# HV_Box_Connector_Board.net
KiCad netlist of a schematic drawn in Altium Designer
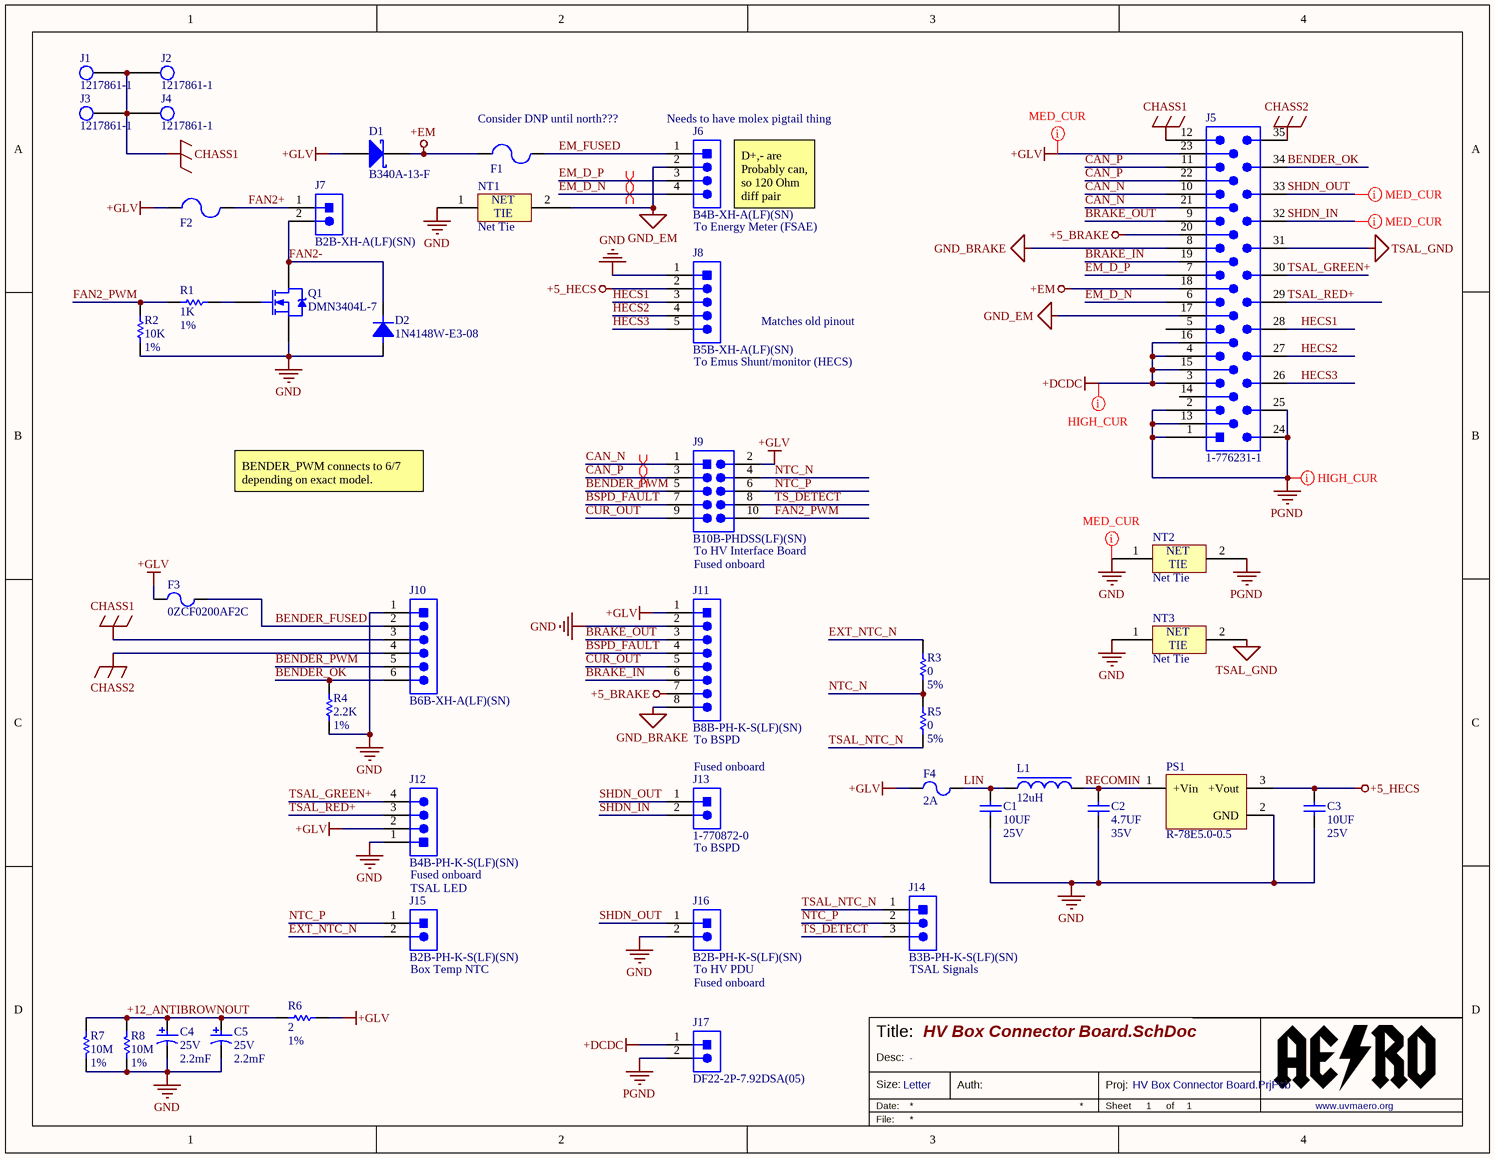
[diagram p0: HV Box Connector Board.SchDoc]

(export (version "E")
  (design (tool "Eeschema 10.0.6"))
  (components
    (comp (ref "C1")
      (value "CAP 0603 10UF 25V 20% X5R")
      (footprint "0603_CAP")
      (description "Capacitor Surface Mount 0603 Footprint 10UF 25V 20% Tolerance Ceramic X5R")
      (fields
        (field (name "VAL") "10UF")
        (field (name "VOL") "25V")
        (field (name "MANUFACTURER") "Various")
        (field (name "VOLTAGE") "25V")
      )
      (libsource (lib "Passive Components") (part "cap"))
    )
    (comp (ref "C2")
      (value "CAP 0603 4.7UF 35V 10% X5R")
      (footprint "0603_CAP")
      (description "Capacitor Surface Mount 0603 Footprint 47UF 35V 10% Tolerance Ceramic X5R")
      (fields
        (field (name "VAL") "4.7UF")
        (field (name "VOL") "35V")
        (field (name "MANUFACTURER") "Various")
        (field (name "VOLTAGE") "35V")
      )
      (libsource (lib "Passive Components") (part "cap"))
    )
    (comp (ref "C3")
      (value "CAP 0603 10UF 25V 20% X5R")
      (footprint "0603_CAP")
      (description "Capacitor Surface Mount 0603 Footprint 10UF 25V 20% Tolerance Ceramic X5R")
      (fields
        (field (name "VAL") "10UF")
        (field (name "VOL") "25V")
        (field (name "MANUFACTURER") "Various")
        (field (name "VOLTAGE") "25V")
      )
      (libsource (lib "Passive Components") (part "cap"))
    )
    (comp (ref "C4")
      (value "URS1E222MHD")
      (footprint "Nichicon_18x15")
      (description "2200µF 25V Aluminum Electrolytic Capacitors Radial, Can  2000 Hrs @ 85°C")
      (fields
        (field (name "MANUFACTURER") "Nichicon")
        (field (name "TOLERANCE") "20%")
        (field (name "VOLTAGE RATING (DC)") "25V")
        (field (name "CAPACITANCE") "2.2mF")
      )
      (libsource (lib "AERO Parts") (part "URS1E222MHD"))
    )
    (comp (ref "C5")
      (value "URS1E222MHD")
      (footprint "Nichicon_18x15")
      (description "2200µF 25V Aluminum Electrolytic Capacitors Radial, Can  2000 Hrs @ 85°C")
      (fields
        (field (name "MANUFACTURER") "Nichicon")
        (field (name "TOLERANCE") "20%")
        (field (name "VOLTAGE RATING (DC)") "25V")
        (field (name "CAPACITANCE") "2.2mF")
      )
      (libsource (lib "AERO Parts") (part "URS1E222MHD"))
    )
    (comp (ref "D1")
      (value "B340A-13-F")
      (footprint "DIOD-SMA-2_V")
      (libsource (lib "Altium Content Vault") (part "DSKY-AK-2"))
    )
    (comp (ref "D2")
      (value "1N4148W-E3-08")
      (footprint "Vishay_1N4148W-E3-08")
      (description "Diode Standard 75V 150mA Surface Mount SOD-123")
      (fields (field (name "MANUFACTURER") "Vishay"))
      (libsource (lib "AERO Parts") (part "1N4148W-E3-08"))
    )
    (comp (ref "F1")
      (value "NANOSMDC050F/13.2-2")
      (footprint "1206_FUSE_40H")
      (description "610 mA 13.2 VDC PTC resettable fuse 1206 footprint")
      (fields (field (name "MANUFACTURER") "Tyco"))
      (libsource (lib "Passive Components") (part "fuse"))
    )
    (comp (ref "F2")
      (value "NANOSMDC050F/13.2-2")
      (footprint "1206_FUSE_40H")
      (description "610 mA 13.2 VDC PTC resettable fuse 1206 footprint")
      (fields (field (name "MANUFACTURER") "Tyco"))
      (libsource (lib "Passive Components") (part "fuse"))
    )
    (comp (ref "F3")
      (value "0ZCF0200AF2C")
      (footprint "Bel_0ZCF0200AF2C_0")
      (description "Polymeric PTC Resettable Fuse 24V 2A Ih Surface Mount 2920 (7351 Metric), Concave")
      (fields (field (name "MANUFACTURER") "Bel"))
      (libsource (lib "AERO Parts") (part "0ZCF0200AF2C"))
    )
    (comp (ref "F4")
      (value "0ZCF0200AF2C")
      (footprint "Bel_0ZCF0200AF2C_0")
      (description "Polymeric PTC Resettable Fuse 24V 2A Ih Surface Mount 2920 (7351 Metric), Concave")
      (fields (field (name "HOLD CURRENT") "2A") (field (name "MANUFACTURER") "Bel"))
      (libsource (lib "AERO Parts") (part "0ZCF0200AF2C"))
    )
    (comp (ref "J1")
      (value "1217861-1")
      (footprint "te-1217861-1")
      (description "CONN TAB .250 STR QC TIN PCB")
      (libsource (lib "AERO Parts") (part "1217861-1"))
    )
    (comp (ref "J2")
      (value "1217861-1")
      (footprint "te-1217861-1")
      (description "CONN TAB .250 STR QC TIN PCB")
      (libsource (lib "AERO Parts") (part "1217861-1"))
    )
    (comp (ref "J3")
      (value "1217861-1")
      (footprint "te-1217861-1")
      (description "CONN TAB .250 STR QC TIN PCB")
      (libsource (lib "AERO Parts") (part "1217861-1"))
    )
    (comp (ref "J4")
      (value "1217861-1")
      (footprint "te-1217861-1")
      (description "CONN TAB .250 STR QC TIN PCB")
      (libsource (lib "AERO Parts") (part "1217861-1"))
    )
    (comp (ref "J5")
      (value "1-776231-1")
      (footprint "TE_1-776231-1")
      (description "Connector Header Panel Mount, Through Hole 35 position 0.157\" (4.00mm)")
      (fields (field (name "MANUFACTURER") "TE Connectivity"))
      (libsource (lib "AERO Parts") (part "1-776231-1"))
    )
    (comp (ref "J6")
      (value "B4B-XH-A(LF)(SN)")
      (footprint "B4B-XH-A(LF)(SN)")
      (description "Connector Header Through Hole 4 position 0.098\" (2.50mm)")
      (fields (field (name "MANUFACTURER") "JST"))
      (libsource (lib "AERO Parts") (part "B4B-XH-A(LF)(SN)"))
    )
    (comp (ref "J7")
      (value "B2B-XH-A(LF)(SN)")
      (footprint "B2B-XH-A(LF)(SN)")
      (description "CONN HEADER VERT 2POS 2.5MM")
      (fields (field (name "MANUFACTURER") "JST"))
      (libsource (lib "AERO Parts") (part "B2B-XH-A(LF)(SN)"))
    )
    (comp (ref "J8")
      (value "B5B-XH-A(LF)(SN)")
      (footprint "JST_B5B-XH-A_LF_SN_0")
      (description "Connector Header Through Hole 5 position 0.098\" (2.50mm)")
      (fields (field (name "MANUFACTURER") "JST"))
      (libsource (lib "AERO Parts") (part "B5B-XH-A(LF)(SN)"))
    )
    (comp (ref "J9")
      (value "B10B-PHDSS(LF)(SN)")
      (footprint "B10B-PHDSS")
      (description "Connector Header Through Hole 10 position 0.079\" (2.00mm)")
      (fields (field (name "MANUFACTURER") "JST"))
      (libsource (lib "AERO Parts") (part "B10B-PHDSS(LF)(SN)"))
    )
    (comp (ref "J10")
      (value "B6B-XH-A(LF)(SN)")
      (footprint "CONN_B6B-XH-A(LF")
      (description "Connector Header Through Hole 6 position 0.098\" (2.50mm)")
      (fields (field (name "MANUFACTURER") "JST") (field (name "MANUFACTURER PART NUMBER") "B6BXHA(LF)(SN)"))
      (libsource (lib "AERO Parts") (part "B6B-XH-A(LF)(SN)"))
    )
    (comp (ref "J11")
      (value "B8B-PH-K-S(LF)(SN)")
      (footprint "B8B-PH-K")
      (description "Connector Header Through Hole 8 position 0.079\" (2.00mm)")
      (libsource (lib "AERO Parts") (part "B8B-PH-K-S(LF)(SN)"))
    )
    (comp (ref "J12")
      (value "B4B-PH-K-S(LF)(SN)")
      (footprint "B4B-PH-K")
      (fields (field (name "MANUFACTURER") "JST"))
      (libsource (lib "AERO Parts") (part "B4B-PH-K-S(LF)(SN)"))
    )
    (comp (ref "J13")
      (value "1-770872-0")
      (footprint "CON2_1X2_P163_VM")
      (description "Connector Header Through Hole 2 position 0.163\" (4.14mm)")
      (fields
        (field (name "MANUFACTURER") "TE Connectivity")
        (field (name "COPYRIGHT") "Copyright (C) 2018 Accelerated Designs. All rights reserved")
      )
      (libsource (lib "AERO Parts") (part "1-770872-0"))
    )
    (comp (ref "J14")
      (value "B3B-PH-K-S(LF)(SN)")
      (footprint "B3B-PH-K")
      (description "Connector Header Through Hole 3 position 0.079\" (2.00mm)")
      (fields (field (name "MANUFACTURER") "JST"))
      (libsource (lib "AERO Parts") (part "B3B-PH-K-S(LF)(SN)"))
    )
    (comp (ref "J15")
      (value "B2B-PH-K-S(LF)(SN)")
      (footprint "JST_Sales_America_Inc._B2B-PH-K-S_LF_SN_0")
      (description "Connector Header Through Hole 2 position 0.079\" (2.00mm)")
      (fields (field (name "MANUFACTURER") "JST") (field (name "MANUFACTURER PART NUMBER") "B2BPHKSLFSN"))
      (libsource (lib "AERO Parts") (part "B2B-PH-K-S(LF)(SN)"))
    )
    (comp (ref "J16")
      (value "B2B-PH-K-S(LF)(SN)")
      (footprint "JST_Sales_America_Inc._B2B-PH-K-S_LF_SN_0")
      (description "Connector Header Through Hole 2 position 0.079\" (2.00mm)")
      (fields (field (name "MANUFACTURER") "JST") (field (name "MANUFACTURER PART NUMBER") "B2BPHKSLFSN"))
      (libsource (lib "AERO Parts") (part "B2B-PH-K-S(LF)(SN)"))
    )
    (comp (ref "J17")
      (value "DF22-2P-7.92DSA(05)")
      (footprint "DF22-2P-7.92DSA_05_0")
      (description "Connector Header Through Hole 2 position 0.312\" (7.92mm)")
      (fields (field (name "MANUFACTURER") "Hirose"))
      (libsource (lib "AERO Parts") (part "DF22-2P-7.92DSA(05)"))
    )
    (comp (ref "L1")
      (value "1225AS-H-120M=P2")
      (footprint "IND_1225AS-H-120M=P2")
      (description "1µH Shielded Wirewound Inductor 15A 4.6mOhm Nonstandard")
      (fields
        (field (name "MANUFACTURER") "Murata")
        (field (name "TOLERANCE") "20%")
        (field (name "INDUCTANCE") "12uH")
      )
      (libsource (lib "AERO Parts") (part "1225AS-H-120M=P2"))
    )
    (comp (ref "NT1")
      (value "Net Tie")
      (footprint "20MIL_TIE")
      (description "Net Tie (No BOM)")
      (libsource (lib "AERO Parts") (part "NET TIE"))
    )
    (comp (ref "NT2")
      (value "Net Tie")
      (footprint "60MIL_TIE")
      (description "Net Tie (No BOM)")
      (libsource (lib "AERO Parts") (part "NET TIE"))
    )
    (comp (ref "NT3")
      (value "Net Tie")
      (footprint "20MIL_TIE")
      (description "Net Tie (No BOM)")
      (libsource (lib "AERO Parts") (part "NET TIE"))
    )
    (comp (ref "PS1")
      (value "R-78E5.0-0.5")
      (footprint "R-78E5.0")
      (description "IC Linear Regulator Replacement DC DC Converter 1 Output 5V 500mA 7V - 28V Input")
      (fields (field (name "DIGIKEY PART NUMBER") "945-1648-5-ND") (field (name "MANUFACTURER") "RECOM"))
      (libsource (lib "AERO Parts") (part "R-78E5.0-0.5"))
    )
    (comp (ref "Q1")
      (value "DMN3404L-7")
      (footprint "SOT23-FET-DI")
      (description "N-Channel 30V 5.8A (Ta) 720mW (Ta) Surface Mount SOT-23-3")
      (fields (field (name "MANUFACTURER") "Diodes"))
      (libsource (lib "AERO Parts") (part "DMN3404L-7"))
    )
    (comp (ref "R1")
      (value "RES 0603 1K 1%")
      (footprint "0603_RES")
      (description "Resistor Surface Mount, 1K Ohms, 0603 Footprint, 1% Tolerance 0.1W")
      (fields
        (field (name "VAL") "1K")
        (field (name "TOL") "1%")
        (field (name "MANUFACTURER") "Various")
        (field (name "TOLERANCE") "1%")
      )
      (libsource (lib "Passive Components") (part "res"))
    )
    (comp (ref "R2")
      (value "RES 0603 10K 1%")
      (footprint "0603_RES")
      (description "Resistor Surface Mount, 10K Ohms, 0603 Footprint, 1% Tolerance 0.1W")
      (fields
        (field (name "VAL") "10K")
        (field (name "TOL") "1%")
        (field (name "MANUFACTURER") "Various")
        (field (name "TOLERANCE") "1%")
      )
      (libsource (lib "Passive Components") (part "res"))
    )
    (comp (ref "R3")
      (value "RES 0603 0 5%")
      (footprint "0603_RES")
      (description "Resistor Surface Mount, 0 Ohms, 0603 Footprint, 5% Tolerance 0.1W")
      (fields
        (field (name "VAL") "0")
        (field (name "TOL") "5%")
        (field (name "MANUFACTURER") "Various")
        (field (name "TOLERANCE") "5%")
      )
      (libsource (lib "Passive Components") (part "res"))
    )
    (comp (ref "R4")
      (value "RES 0603 2.2K 1%")
      (footprint "0603_RES")
      (description "Resistor Surface Mount, 2.2K Ohms, 0603 Footprint, 1% Tolerance 0.1W")
      (fields
        (field (name "VAL") "2.2K")
        (field (name "TOL") "1%")
        (field (name "MANUFACTURER") "Various")
        (field (name "TOLERANCE") "1%")
      )
      (libsource (lib "Passive Components") (part "res"))
    )
    (comp (ref "R5")
      (value "RES 0603 0 5%")
      (footprint "0603_RES")
      (description "Resistor Surface Mount, 0 Ohms, 0603 Footprint, 5% Tolerance 0.1W")
      (fields
        (field (name "VAL") "0")
        (field (name "TOL") "5%")
        (field (name "MANUFACTURER") "Various")
        (field (name "TOLERANCE") "5%")
      )
      (libsource (lib "Passive Components") (part "res"))
    )
    (comp (ref "R6")
      (value "RES 1206 2 1%")
      (footprint "1206_RES_28H")
      (description "Resistor Surface Mount, 2 Ohms, 1206 Footprint, 1% Tolerance 0.25W")
      (fields
        (field (name "VAL") "2")
        (field (name "TOL") "1%")
        (field (name "MANUFACTURER") "Various")
        (field (name "TOLERANCE") "1%")
      )
      (libsource (lib "Passive Components") (part "res"))
    )
    (comp (ref "R7")
      (value "RES 0805 10M 1%")
      (footprint "0805_RES")
      (description "Resistor Surface Mount, 10M Ohms, 0805 Footprint, 1% Tolerance 0.125W")
      (fields
        (field (name "VAL") "10M")
        (field (name "TOL") "1%")
        (field (name "MANUFACTURER") "Various")
        (field (name "TOLERANCE") "1%")
      )
      (libsource (lib "Passive Components") (part "res"))
    )
    (comp (ref "R8")
      (value "RES 0805 10M 1%")
      (footprint "0805_RES")
      (description "Resistor Surface Mount, 10M Ohms, 0805 Footprint, 1% Tolerance 0.125W")
      (fields
        (field (name "VAL") "10M")
        (field (name "TOL") "1%")
        (field (name "MANUFACTURER") "Various")
        (field (name "TOLERANCE") "1%")
      )
      (libsource (lib "Passive Components") (part "res"))
    )
  )
  (nets
    (net (code "1") (name "+5_BRAKE") (class "Default")
      (node (ref "J11") (pin "7") (pinfunction "7_7") (pintype "passive"))
      (node (ref "J5") (pin "20") (pinfunction "20_20") (pintype "passive"))
    )
    (net (code "2") (name "+5_HECS") (class "Default")
      (node (ref "C3") (pin "2") (pinfunction "2_2") (pintype "passive"))
      (node (ref "J8") (pin "2") (pinfunction "2_2") (pintype "passive"))
      (node (ref "PS1") (pin "3") (pinfunction "+Vout_3") (pintype "power_in"))
    )
    (net (code "3") (name "+DCDC") (class "Default")
      (node (ref "J17") (pin "1") (pinfunction "1_1") (pintype "passive"))
      (node (ref "J5") (pin "15") (pinfunction "15_15") (pintype "passive"))
      (node (ref "J5") (pin "16") (pinfunction "16_16") (pintype "passive"))
      (node (ref "J5") (pin "3") (pinfunction "3_3") (pintype "passive"))
      (node (ref "J5") (pin "4") (pinfunction "4_4") (pintype "passive"))
    )
    (net (code "4") (name "+EM") (class "Default")
      (node (ref "D1") (pin "2") (pinfunction "K_2") (pintype "passive"))
      (node (ref "F1") (pin "1") (pinfunction "1_1") (pintype "passive"))
      (node (ref "J5") (pin "18") (pinfunction "18_18") (pintype "passive"))
    )
    (net (code "5") (name "+GLV") (class "Default")
      (node (ref "D1") (pin "1") (pinfunction "A_1") (pintype "passive"))
      (node (ref "F2") (pin "1") (pinfunction "1_1") (pintype "passive"))
      (node (ref "F3") (pin "1") (pinfunction "1_1") (pintype "passive"))
      (node (ref "F4") (pin "1") (pinfunction "1_1") (pintype "passive"))
      (node (ref "J11") (pin "1") (pinfunction "1_1") (pintype "passive"))
      (node (ref "J12") (pin "2") (pinfunction "2_2") (pintype "passive"))
      (node (ref "J5") (pin "23") (pinfunction "23_23") (pintype "passive"))
      (node (ref "J9") (pin "2") (pinfunction "2_2") (pintype "passive"))
      (node (ref "R6") (pin "2") (pinfunction "2_2") (pintype "passive"))
    )
    (net (code "6") (name "/+12_ANTIBROWNOUT") (class "Default")
      (node (ref "C4") (pin "1") (pinfunction "1_1") (pintype "passive"))
      (node (ref "C5") (pin "1") (pinfunction "1_1") (pintype "passive"))
      (node (ref "R6") (pin "1") (pinfunction "1_1") (pintype "passive"))
      (node (ref "R7") (pin "2") (pinfunction "2_2") (pintype "passive"))
      (node (ref "R8") (pin "2") (pinfunction "2_2") (pintype "passive"))
    )
    (net (code "7") (name "/BENDER_FUSED") (class "Default")
      (node (ref "F3") (pin "2") (pinfunction "2_2") (pintype "passive"))
      (node (ref "J10") (pin "2") (pinfunction "2_2") (pintype "passive"))
    )
    (net (code "8") (name "/BENDER_OK") (class "Default")
      (node (ref "J10") (pin "6") (pinfunction "6_6") (pintype "passive"))
      (node (ref "J5") (pin "34") (pinfunction "34_34") (pintype "passive"))
      (node (ref "R4") (pin "1") (pinfunction "1_1") (pintype "passive"))
    )
    (net (code "9") (name "/BENDER_PWM") (class "Default")
      (node (ref "J10") (pin "5") (pinfunction "5_5") (pintype "passive"))
      (node (ref "J9") (pin "5") (pinfunction "5_5") (pintype "passive"))
    )
    (net (code "10") (name "/BRAKE_IN") (class "Default")
      (node (ref "J11") (pin "6") (pinfunction "6_6") (pintype "passive"))
      (node (ref "J5") (pin "19") (pinfunction "19_19") (pintype "passive"))
    )
    (net (code "11") (name "/BRAKE_OUT") (class "Default")
      (node (ref "J11") (pin "3") (pinfunction "3_3") (pintype "passive"))
      (node (ref "J5") (pin "9") (pinfunction "9_9") (pintype "passive"))
    )
    (net (code "12") (name "/BSPD_FAULT") (class "Default")
      (node (ref "J11") (pin "4") (pinfunction "4_4") (pintype "passive"))
      (node (ref "J9") (pin "7") (pinfunction "7_7") (pintype "passive"))
    )
    (net (code "13") (name "/CAN_N") (class "Default")
      (node (ref "J5") (pin "10") (pinfunction "10_10") (pintype "passive"))
      (node (ref "J5") (pin "21") (pinfunction "21_21") (pintype "passive"))
      (node (ref "J9") (pin "1") (pinfunction "1_1") (pintype "passive"))
    )
    (net (code "14") (name "/CAN_P") (class "Default")
      (node (ref "J5") (pin "11") (pinfunction "11_11") (pintype "passive"))
      (node (ref "J5") (pin "22") (pinfunction "22_22") (pintype "passive"))
      (node (ref "J9") (pin "3") (pinfunction "3_3") (pintype "passive"))
    )
    (net (code "15") (name "/CUR_OUT") (class "Default")
      (node (ref "J11") (pin "5") (pinfunction "5_5") (pintype "passive"))
      (node (ref "J9") (pin "9") (pinfunction "9_9") (pintype "passive"))
    )
    (net (code "16") (name "/EM_D_N") (class "Default")
      (node (ref "J5") (pin "6") (pinfunction "6_6") (pintype "passive"))
      (node (ref "J6") (pin "4") (pinfunction "4_4") (pintype "passive"))
    )
    (net (code "17") (name "/EM_D_P") (class "Default")
      (node (ref "J5") (pin "7") (pinfunction "7_7") (pintype "passive"))
      (node (ref "J6") (pin "3") (pinfunction "3_3") (pintype "passive"))
    )
    (net (code "18") (name "/EM_FUSED") (class "Default")
      (node (ref "F1") (pin "2") (pinfunction "2_2") (pintype "passive"))
      (node (ref "J6") (pin "1") (pinfunction "1_1") (pintype "passive"))
    )
    (net (code "19") (name "/EXT_NTC_N") (class "Default")
      (node (ref "J15") (pin "2") (pinfunction "2_2") (pintype "passive"))
      (node (ref "R3") (pin "2") (pinfunction "2_2") (pintype "passive"))
    )
    (net (code "20") (name "/FAN2+") (class "Default")
      (node (ref "F2") (pin "2") (pinfunction "2_2") (pintype "passive"))
      (node (ref "J7") (pin "1") (pinfunction "1_1") (pintype "passive"))
    )
    (net (code "21") (name "/FAN2-") (class "Default")
      (node (ref "D2") (pin "K") (pinfunction "K_K") (pintype "passive"))
      (node (ref "J7") (pin "2") (pinfunction "2_2") (pintype "passive"))
      (node (ref "Q1") (pin "3") (pinfunction "D_3") (pintype "passive"))
    )
    (net (code "22") (name "/FAN2_PWM") (class "Default")
      (node (ref "J9") (pin "10") (pinfunction "10_10") (pintype "passive"))
      (node (ref "R1") (pin "1") (pinfunction "1_1") (pintype "passive"))
      (node (ref "R2") (pin "2") (pinfunction "2_2") (pintype "passive"))
    )
    (net (code "23") (name "/HECS1") (class "Default")
      (node (ref "J5") (pin "28") (pinfunction "28_28") (pintype "passive"))
      (node (ref "J8") (pin "3") (pinfunction "3_3") (pintype "passive"))
    )
    (net (code "24") (name "/HECS2") (class "Default")
      (node (ref "J5") (pin "27") (pinfunction "27_27") (pintype "passive"))
      (node (ref "J8") (pin "4") (pinfunction "4_4") (pintype "passive"))
    )
    (net (code "25") (name "/HECS3") (class "Default")
      (node (ref "J5") (pin "26") (pinfunction "26_26") (pintype "passive"))
      (node (ref "J8") (pin "5") (pinfunction "5_5") (pintype "passive"))
    )
    (net (code "26") (name "/LIN") (class "Default")
      (node (ref "C1") (pin "2") (pinfunction "2_2") (pintype "passive"))
      (node (ref "F4") (pin "2") (pinfunction "2_2") (pintype "passive"))
      (node (ref "L1") (pin "1") (pinfunction "1_1") (pintype "passive"))
    )
    (net (code "27") (name "/NTC_N") (class "Default")
      (node (ref "J9") (pin "4") (pinfunction "4_4") (pintype "passive"))
      (node (ref "R3") (pin "1") (pinfunction "1_1") (pintype "passive"))
      (node (ref "R5") (pin "2") (pinfunction "2_2") (pintype "passive"))
    )
    (net (code "28") (name "/NTC_P") (class "Default")
      (node (ref "J14") (pin "2") (pinfunction "2_2") (pintype "passive"))
      (node (ref "J15") (pin "1") (pinfunction "1_1") (pintype "passive"))
      (node (ref "J9") (pin "6") (pinfunction "6_6") (pintype "passive"))
    )
    (net (code "29") (name "/RECOMIN") (class "Default")
      (node (ref "C2") (pin "2") (pinfunction "2_2") (pintype "passive"))
      (node (ref "L1") (pin "2") (pinfunction "2_2") (pintype "passive"))
      (node (ref "PS1") (pin "1") (pinfunction "+Vin_1") (pintype "power_in"))
    )
    (net (code "30") (name "/SHDN_IN") (class "Default")
      (node (ref "J13") (pin "2") (pinfunction "2_2") (pintype "passive"))
      (node (ref "J5") (pin "32") (pinfunction "32_32") (pintype "passive"))
    )
    (net (code "31") (name "/SHDN_OUT") (class "Default")
      (node (ref "J13") (pin "1") (pinfunction "1_1") (pintype "passive"))
      (node (ref "J16") (pin "1") (pinfunction "1_1") (pintype "passive"))
      (node (ref "J5") (pin "33") (pinfunction "33_33") (pintype "passive"))
    )
    (net (code "32") (name "/TSAL_GREEN+") (class "Default")
      (node (ref "J12") (pin "4") (pinfunction "4_4") (pintype "passive"))
      (node (ref "J5") (pin "30") (pinfunction "30_30") (pintype "passive"))
    )
    (net (code "33") (name "/TSAL_NTC_N") (class "Default")
      (node (ref "J14") (pin "1") (pinfunction "1_1") (pintype "passive"))
      (node (ref "R5") (pin "1") (pinfunction "1_1") (pintype "passive"))
    )
    (net (code "34") (name "/TSAL_RED+") (class "Default")
      (node (ref "J12") (pin "3") (pinfunction "3_3") (pintype "passive"))
      (node (ref "J5") (pin "29") (pinfunction "29_29") (pintype "passive"))
    )
    (net (code "35") (name "/TS_DETECT") (class "Default")
      (node (ref "J14") (pin "3") (pinfunction "3_3") (pintype "passive"))
      (node (ref "J9") (pin "8") (pinfunction "8_8") (pintype "passive"))
    )
    (net (code "36") (name "CHASS1") (class "Default")
      (node (ref "J1") (pin "1a") (pinfunction "1a_1a") (pintype "passive"))
      (node (ref "J1") (pin "1b") (pinfunction "1b_1b") (pintype "passive"))
      (node (ref "J1") (pin "1c") (pinfunction "1c_1c") (pintype "passive"))
      (node (ref "J10") (pin "3") (pinfunction "3_3") (pintype "passive"))
      (node (ref "J2") (pin "1a") (pinfunction "1a_1a") (pintype "passive"))
      (node (ref "J2") (pin "1b") (pinfunction "1b_1b") (pintype "passive"))
      (node (ref "J2") (pin "1c") (pinfunction "1c_1c") (pintype "passive"))
      (node (ref "J3") (pin "1a") (pinfunction "1a_1a") (pintype "passive"))
      (node (ref "J3") (pin "1b") (pinfunction "1b_1b") (pintype "passive"))
      (node (ref "J3") (pin "1c") (pinfunction "1c_1c") (pintype "passive"))
      (node (ref "J4") (pin "1a") (pinfunction "1a_1a") (pintype "passive"))
      (node (ref "J4") (pin "1b") (pinfunction "1b_1b") (pintype "passive"))
      (node (ref "J4") (pin "1c") (pinfunction "1c_1c") (pintype "passive"))
      (node (ref "J5") (pin "12") (pinfunction "12_12") (pintype "passive"))
    )
    (net (code "37") (name "CHASS2") (class "Default")
      (node (ref "J10") (pin "4") (pinfunction "4_4") (pintype "passive"))
      (node (ref "J5") (pin "35") (pinfunction "35_35") (pintype "passive"))
    )
    (net (code "38") (name "GND") (class "Default")
      (node (ref "C1") (pin "1") (pinfunction "1_1") (pintype "passive"))
      (node (ref "C2") (pin "1") (pinfunction "1_1") (pintype "passive"))
      (node (ref "C3") (pin "1") (pinfunction "1_1") (pintype "passive"))
      (node (ref "C4") (pin "2") (pinfunction "2_2") (pintype "passive"))
      (node (ref "C5") (pin "2") (pinfunction "2_2") (pintype "passive"))
      (node (ref "D2") (pin "A") (pinfunction "A_A") (pintype "passive"))
      (node (ref "J10") (pin "1") (pinfunction "1_1") (pintype "passive"))
      (node (ref "J11") (pin "2") (pinfunction "2_2") (pintype "passive"))
      (node (ref "J12") (pin "1") (pinfunction "1_1") (pintype "passive"))
      (node (ref "J16") (pin "2") (pinfunction "2_2") (pintype "passive"))
      (node (ref "J8") (pin "1") (pinfunction "1_1") (pintype "passive"))
      (node (ref "NT1") (pin "1") (pintype "passive"))
      (node (ref "NT2") (pin "1") (pintype "passive"))
      (node (ref "NT3") (pin "1") (pintype "passive"))
      (node (ref "PS1") (pin "2") (pinfunction "GND_2") (pintype "power_in"))
      (node (ref "Q1") (pin "2") (pinfunction "S_2") (pintype "passive"))
      (node (ref "R2") (pin "1") (pinfunction "1_1") (pintype "passive"))
      (node (ref "R4") (pin "2") (pinfunction "2_2") (pintype "passive"))
      (node (ref "R7") (pin "1") (pinfunction "1_1") (pintype "passive"))
      (node (ref "R8") (pin "1") (pinfunction "1_1") (pintype "passive"))
    )
    (net (code "39") (name "GND_BRAKE") (class "Default")
      (node (ref "J11") (pin "8") (pinfunction "8_8") (pintype "passive"))
      (node (ref "J5") (pin "8") (pinfunction "8_8") (pintype "passive"))
    )
    (net (code "40") (name "GND_EM") (class "Default")
      (node (ref "J5") (pin "17") (pinfunction "17_17") (pintype "passive"))
      (node (ref "J6") (pin "2") (pinfunction "2_2") (pintype "passive"))
      (node (ref "NT1") (pin "2") (pintype "passive"))
    )
    (net (code "41") (name "Net-(Q1-G)") (class "Default")
      (node (ref "Q1") (pin "1") (pinfunction "G_1") (pintype "passive"))
      (node (ref "R1") (pin "2") (pinfunction "2_2") (pintype "passive"))
    )
    (net (code "42") (name "PGND") (class "Default")
      (node (ref "J17") (pin "2") (pinfunction "2_2") (pintype "passive"))
      (node (ref "J5") (pin "1") (pinfunction "1_1") (pintype "passive"))
      (node (ref "J5") (pin "13") (pinfunction "13_13") (pintype "passive"))
      (node (ref "J5") (pin "2") (pinfunction "2_2") (pintype "passive"))
      (node (ref "J5") (pin "24") (pinfunction "24_24") (pintype "passive"))
      (node (ref "J5") (pin "25") (pinfunction "25_25") (pintype "passive"))
      (node (ref "NT2") (pin "2") (pintype "passive"))
    )
    (net (code "43") (name "TSAL_GND") (class "Default")
      (node (ref "J5") (pin "31") (pinfunction "31_31") (pintype "passive"))
      (node (ref "NT3") (pin "2") (pintype "passive"))
    )
    (net (code "44") (name "unconnected-(J5-Pad5)") (class "Default")
      (node (ref "J5") (pin "5") (pinfunction "5_5") (pintype "passive"))
    )
    (net (code "45") (name "unconnected-(J5-Pad14)") (class "Default")
      (node (ref "J5") (pin "14") (pinfunction "14_14") (pintype "passive"))
    )
  )
)
